# Sensor2.net
KiCad netlist of a schematic drawn in Altium Designer
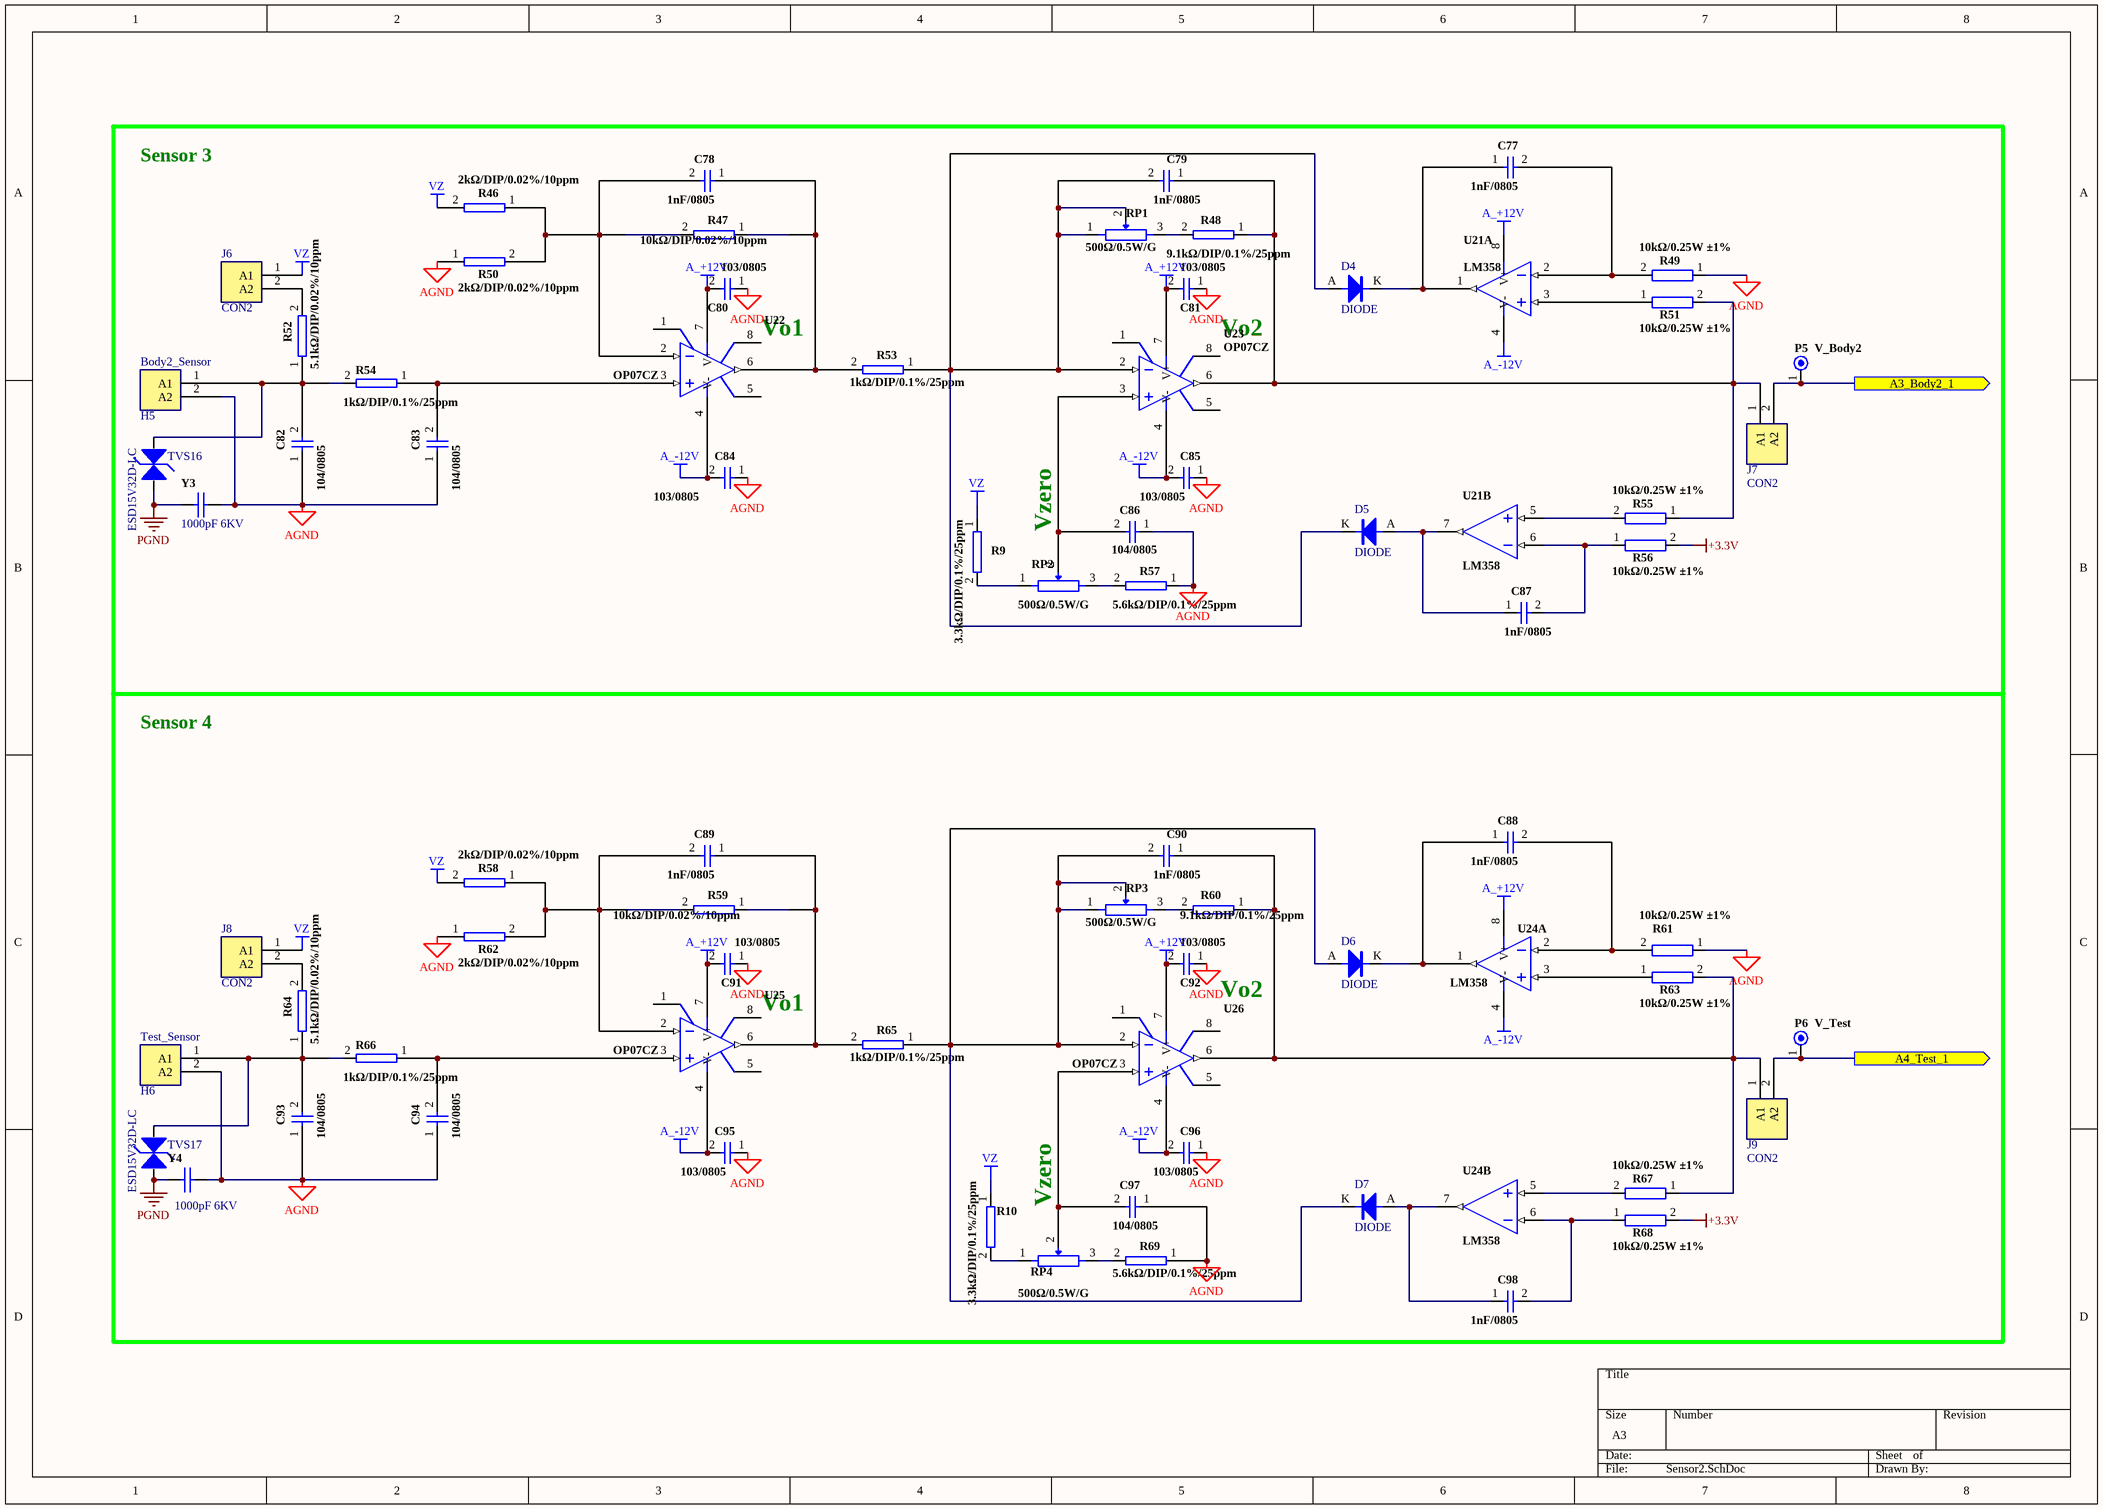
[diagram p0: Sensor2.SchDoc]

(export (version "E")
  (design (tool "Eeschema 10.0.6"))
  (components
    (comp (ref "C77")
      (value "1nF/0805")
      (footprint "C0805")
      (description "贴片电容 1nF/25V ±1% C0805")
      (libsource (lib "COOLCONTROL") (part "CAP"))
    )
    (comp (ref "C78")
      (value "1nF/0805")
      (footprint "C0805")
      (description "贴片电容 1nF/25V ±1% C0805")
      (libsource (lib "COOLCONTROL") (part "CAP"))
    )
    (comp (ref "C79")
      (value "1nF/0805")
      (footprint "C0805")
      (description "贴片电容 1nF/25V ±1% C0805")
      (libsource (lib "COOLCONTROL") (part "CAP"))
    )
    (comp (ref "C80")
      (value "103/0805")
      (footprint "C0805")
      (description "贴片电容 103/25V ±1% C0805")
      (libsource (lib "COOLCONTROL") (part "CAP"))
    )
    (comp (ref "C81")
      (value "103/0805")
      (footprint "C0805")
      (description "贴片电容 103/25V ±1% C0805")
      (libsource (lib "COOLCONTROL") (part "CAP"))
    )
    (comp (ref "C82")
      (value "104/0805")
      (footprint "C0805")
      (description "贴片电容 104/25V ±1% C0805")
      (libsource (lib "COOLCONTROL") (part "CAP"))
    )
    (comp (ref "C83")
      (value "104/0805")
      (footprint "C0805")
      (description "贴片电容 104/25V ±1% C0805")
      (libsource (lib "COOLCONTROL") (part "CAP"))
    )
    (comp (ref "C84")
      (value "103/0805")
      (footprint "C0805")
      (description "贴片电容 103/25V ±1% C0805")
      (libsource (lib "COOLCONTROL") (part "CAP"))
    )
    (comp (ref "C85")
      (value "103/0805")
      (footprint "C0805")
      (description "贴片电容 103/25V ±1% C0805")
      (libsource (lib "COOLCONTROL") (part "CAP"))
    )
    (comp (ref "C86")
      (value "104/0805")
      (footprint "C0805")
      (description "贴片电容 104/25V ±1% C0805")
      (libsource (lib "COOLCONTROL") (part "CAP"))
    )
    (comp (ref "C87")
      (value "1nF/0805")
      (footprint "C0805")
      (description "贴片电容 1nF/25V ±1% C0805")
      (libsource (lib "COOLCONTROL") (part "CAP"))
    )
    (comp (ref "C88")
      (value "1nF/0805")
      (footprint "C0805")
      (description "贴片电容 1nF/25V ±1% C0805")
      (libsource (lib "COOLCONTROL") (part "CAP"))
    )
    (comp (ref "C89")
      (value "1nF/0805")
      (footprint "C0805")
      (description "贴片电容 1nF/25V ±1% C0805")
      (libsource (lib "COOLCONTROL") (part "CAP"))
    )
    (comp (ref "C90")
      (value "1nF/0805")
      (footprint "C0805")
      (description "贴片电容 1nF/25V ±1% C0805")
      (libsource (lib "COOLCONTROL") (part "CAP"))
    )
    (comp (ref "C91")
      (value "103/0805")
      (footprint "C0805")
      (description "贴片电容 103/25V ±1% C0805")
      (libsource (lib "COOLCONTROL") (part "CAP"))
    )
    (comp (ref "C92")
      (value "103/0805")
      (footprint "C0805")
      (description "贴片电容 103/25V ±1% C0805")
      (libsource (lib "COOLCONTROL") (part "CAP"))
    )
    (comp (ref "C93")
      (value "104/0805")
      (footprint "C0805")
      (description "贴片电容 104/25V ±1% C0805")
      (libsource (lib "COOLCONTROL") (part "CAP"))
    )
    (comp (ref "C94")
      (value "104/0805")
      (footprint "C0805")
      (description "贴片电容 104/25V ±1% C0805")
      (libsource (lib "COOLCONTROL") (part "CAP"))
    )
    (comp (ref "C95")
      (value "103/0805")
      (footprint "C0805")
      (description "贴片电容 103/25V ±1% C0805")
      (libsource (lib "COOLCONTROL") (part "CAP"))
    )
    (comp (ref "C96")
      (value "103/0805")
      (footprint "C0805")
      (description "贴片电容 103/25V ±1% C0805")
      (libsource (lib "COOLCONTROL") (part "CAP"))
    )
    (comp (ref "C97")
      (value "104/0805")
      (footprint "C0805")
      (description "贴片电容 104/25V ±1% C0805")
      (libsource (lib "COOLCONTROL") (part "CAP"))
    )
    (comp (ref "C98")
      (value "1nF/0805")
      (footprint "C0805")
      (description "贴片电容 1nF/25V ±1% C0805")
      (libsource (lib "COOLCONTROL") (part "CAP"))
    )
    (comp (ref "D4")
      (value "DIODE")
      (footprint "SOD123")
      (description "高速开关二极管 IN4148 1V 150mA SOD123")
      (libsource (lib "") (part "DIODE_1"))
    )
    (comp (ref "D5")
      (value "DIODE")
      (footprint "SOD123")
      (description "高速开关二极管 IN4148 1V 150mA SOD123")
      (libsource (lib "COOLCONTROL") (part "DIODE"))
    )
    (comp (ref "D6")
      (value "DIODE")
      (footprint "SOD123")
      (description "高速开关二极管 IN4148 1V 150mA SOD123")
      (libsource (lib "") (part "DIODE_1"))
    )
    (comp (ref "D7")
      (value "DIODE")
      (footprint "SOD123")
      (description "高速开关二极管 IN4148 1V 150mA SOD123")
      (libsource (lib "COOLCONTROL") (part "DIODE"))
    )
    (comp (ref "H5")
      (value "Body2_Sensor")
      (footprint "XH2")
      (description "插座式端子 XH2.54-2P 250V(DC/AC) 3A")
      (libsource (lib "COOLCONTROL") (part "CON2"))
    )
    (comp (ref "H6")
      (value "Test_Sensor")
      (footprint "XH2")
      (description "插座式端子 XH2.54-2P 250V(DC/AC) 3A")
      (libsource (lib "COOLCONTROL") (part "CON2"))
    )
    (comp (ref "J6")
      (value "CON2")
      (footprint "2Pin-2.54")
      (description "单排排针（2针）2.54mm 2Pin-2.54")
      (libsource (lib "COOLCONTROL") (part "CON2"))
    )
    (comp (ref "J7")
      (value "CON2")
      (footprint "2Pin-2.54")
      (description "单排排针（2针）2.54mm 2Pin-2.54")
      (libsource (lib "") (part "CON2_1"))
    )
    (comp (ref "J8")
      (value "CON2")
      (footprint "2Pin-2.54")
      (description "单排排针（2针）2.54mm 2Pin-2.54")
      (libsource (lib "COOLCONTROL") (part "CON2"))
    )
    (comp (ref "J9")
      (value "CON2")
      (footprint "2Pin-2.54")
      (description "单排排针（2针）2.54mm 2Pin-2.54")
      (libsource (lib "") (part "CON2_1"))
    )
    (comp (ref "P5")
      (value "V_Body2")
      (footprint "COOLCONTROL:TESTSMD")
      (libsource (lib "COOLCONTROL") (part "CON1"))
    )
    (comp (ref "P6")
      (value "V_Test")
      (footprint "COOLCONTROL:TESTSMD")
      (libsource (lib "COOLCONTROL") (part "CON1"))
    )
    (comp (ref "R9")
      (value "3.3kΩ/DIP/0.1%/25ppm")
      (footprint "COOLCONTROL:AXIAL0.4")
      (description "高精度电阻 3.3kΩ DIP 0.25W ±0.1% 25ppm AXIAL0.4")
      (libsource (lib "COOLCONTROL") (part "RES2"))
    )
    (comp (ref "R10")
      (value "3.3kΩ/DIP/0.1%/25ppm")
      (footprint "COOLCONTROL:AXIAL0.4")
      (description "高精度电阻 3.3kΩ DIP 0.25W ±0.1% 25ppm AXIAL0.4")
      (libsource (lib "COOLCONTROL") (part "RES2"))
    )
    (comp (ref "R46")
      (value "2kΩ/DIP/0.02%/10ppm")
      (footprint "AXIAL-0.6-R")
      (description "高精度电阻 2kΩ DIP 0.25W ±0.02% 10ppm AXIAL-0.6-R")
      (libsource (lib "COOLCONTROL") (part "RES2"))
    )
    (comp (ref "R47")
      (value "10kΩ/DIP/0.02%/10ppm")
      (footprint "AXIAL-0.6-R")
      (description "高精度电阻 10kΩ DIP 0.25W ±0.02% 10ppm AXIAL-0.6-R")
      (libsource (lib "COOLCONTROL") (part "RES2"))
    )
    (comp (ref "R48")
      (value "9.1kΩ/DIP/0.1%/25ppm")
      (footprint "COOLCONTROL:AXIAL0.4")
      (description "高精度电阻 9.1kΩ DIP 0.25W ±0.1% 25ppm AXIAL0.4")
      (libsource (lib "COOLCONTROL") (part "RES2"))
    )
    (comp (ref "R49")
      (value "10kΩ/0.25W ±1%")
      (footprint "R0805")
      (description "贴片电阻 10kΩ 0.25W ±1% R0805")
      (libsource (lib "") (part "RES2_1"))
    )
    (comp (ref "R50")
      (value "2kΩ/DIP/0.02%/10ppm")
      (footprint "AXIAL-0.6-R")
      (description "高精度电阻 2kΩ DIP 0.25W ±0.02% 10ppm AXIAL-0.6-R")
      (libsource (lib "COOLCONTROL") (part "RES2"))
    )
    (comp (ref "R51")
      (value "10kΩ/0.25W ±1%")
      (footprint "R0805")
      (description "贴片电阻 10kΩ 0.25W ±1% R0805")
      (libsource (lib "") (part "RES2_2"))
    )
    (comp (ref "R52")
      (value "5.1kΩ/DIP/0.02%/10ppm")
      (footprint "AXIAL-0.6-R")
      (description "高精度电阻 5.1kΩ DIP 0.25W ±0.02% 10ppm AXIAL-0.6-R")
      (libsource (lib "COOLCONTROL") (part "RES2"))
    )
    (comp (ref "R53")
      (value "1kΩ/DIP/0.1%/25ppm")
      (footprint "COOLCONTROL:AXIAL0.4")
      (description "高精度电阻 1kΩ DIP 0.25W ±0.1% 25ppm AXIAL0.4")
      (libsource (lib "COOLCONTROL") (part "RES2"))
    )
    (comp (ref "R54")
      (value "1kΩ/DIP/0.1%/25ppm")
      (footprint "COOLCONTROL:AXIAL0.4")
      (description "高精度电阻 1kΩ DIP 0.25W ±0.1% 25ppm AXIAL0.4")
      (libsource (lib "COOLCONTROL") (part "RES2"))
    )
    (comp (ref "R55")
      (value "10kΩ/0.25W ±1%")
      (footprint "R0805")
      (description "贴片电阻 10kΩ 0.25W ±1% R0805")
      (libsource (lib "") (part "RES2_1"))
    )
    (comp (ref "R56")
      (value "10kΩ/0.25W ±1%")
      (footprint "R0805")
      (description "贴片电阻 10kΩ 0.25W ±1% R0805")
      (libsource (lib "") (part "RES2_2"))
    )
    (comp (ref "R57")
      (value "5.6kΩ/DIP/0.1%/25ppm")
      (footprint "COOLCONTROL:AXIAL0.4")
      (description "高精度电阻 5.6kΩ DIP 0.25W ±0.1% 25ppm AXIAL0.4")
      (libsource (lib "COOLCONTROL") (part "RES2"))
    )
    (comp (ref "R58")
      (value "2kΩ/DIP/0.02%/10ppm")
      (footprint "AXIAL-0.6-R")
      (description "高精度电阻 2kΩ DIP 0.25W ±0.02% 10ppm AXIAL-0.6-R")
      (libsource (lib "COOLCONTROL") (part "RES2"))
    )
    (comp (ref "R59")
      (value "10kΩ/DIP/0.02%/10ppm")
      (footprint "AXIAL-0.6-R")
      (description "高精度电阻 10kΩ DIP 0.25W ±0.02% 10ppm AXIAL-0.6-R")
      (libsource (lib "COOLCONTROL") (part "RES2"))
    )
    (comp (ref "R60")
      (value "9.1kΩ/DIP/0.1%/25ppm")
      (footprint "COOLCONTROL:AXIAL0.4")
      (description "高精度电阻 9.1kΩ DIP 0.25W ±0.1% 25ppm AXIAL0.4")
      (libsource (lib "COOLCONTROL") (part "RES2"))
    )
    (comp (ref "R61")
      (value "10kΩ/0.25W ±1%")
      (footprint "R0805")
      (description "贴片电阻 10kΩ 0.25W ±1% R0805")
      (libsource (lib "") (part "RES2_1"))
    )
    (comp (ref "R62")
      (value "2kΩ/DIP/0.02%/10ppm")
      (footprint "AXIAL-0.6-R")
      (description "高精度电阻 2kΩ DIP 0.25W ±0.02% 10ppm AXIAL-0.6-R")
      (libsource (lib "COOLCONTROL") (part "RES2"))
    )
    (comp (ref "R63")
      (value "10kΩ/0.25W ±1%")
      (footprint "R0805")
      (description "贴片电阻 10kΩ 0.25W ±1% R0805")
      (libsource (lib "") (part "RES2_2"))
    )
    (comp (ref "R64")
      (value "5.1kΩ/DIP/0.02%/10ppm")
      (footprint "AXIAL-0.6-R")
      (description "高精度电阻 5.1kΩ DIP 0.25W ±0.02% 10ppm AXIAL-0.6-R")
      (libsource (lib "COOLCONTROL") (part "RES2"))
    )
    (comp (ref "R65")
      (value "1kΩ/DIP/0.1%/25ppm")
      (footprint "COOLCONTROL:AXIAL0.4")
      (description "高精度电阻 1kΩ DIP 0.25W ±0.1% 25ppm AXIAL0.4")
      (libsource (lib "COOLCONTROL") (part "RES2"))
    )
    (comp (ref "R66")
      (value "1kΩ/DIP/0.1%/25ppm")
      (footprint "AXIAL0.4")
      (description "高精度电阻 1kΩ DIP 0.25W ±0.1% 25ppm AXIAL0.4")
      (libsource (lib "COOLCONTROL") (part "RES2"))
    )
    (comp (ref "R67")
      (value "10kΩ/0.25W ±1%")
      (footprint "R0805")
      (description "贴片电阻 10kΩ 0.25W ±1% R0805")
      (libsource (lib "") (part "RES2_1"))
    )
    (comp (ref "R68")
      (value "10kΩ/0.25W ±1%")
      (footprint "R0805")
      (description "贴片电阻 10kΩ 0.25W ±1% R0805")
      (libsource (lib "") (part "RES2_2"))
    )
    (comp (ref "R69")
      (value "5.6kΩ/DIP/0.1%/25ppm")
      (footprint "COOLCONTROL:AXIAL0.4")
      (description "高精度电阻 5.6kΩ DIP 0.25W ±0.1% 25ppm AXIAL0.4")
      (libsource (lib "COOLCONTROL") (part "RES2"))
    )
    (comp (ref "RP1")
      (value "500Ω/0.5W/G")
      (footprint "3224W")
      (description "高精密可调电位器 500Ω/0.5W/G 3224W")
      (libsource (lib "COOLCONTROL") (part "RPOT"))
    )
    (comp (ref "RP2")
      (value "500Ω/0.5W/G")
      (footprint "3224W")
      (description "高精密可调电位器 500Ω/0.5W/G 3224W")
      (libsource (lib "COOLCONTROL") (part "RPOT"))
    )
    (comp (ref "RP3")
      (value "500Ω/0.5W/G")
      (footprint "3224W")
      (description "高精密可调电位器 500Ω/0.5W/G 3224W")
      (libsource (lib "COOLCONTROL") (part "RPOT"))
    )
    (comp (ref "RP4")
      (value "500Ω/0.5W/G")
      (footprint "3224W")
      (description "高精密可调电位器 500Ω/0.5W/G 3224W")
      (libsource (lib "COOLCONTROL") (part "RPOT"))
    )
    (comp (ref "TVS16")
      (value "ESD15V32D-LC")
      (footprint "SOD323")
      (description "ESD静电二极管 ESD15V32D-LC 15V 15KV 40A SOD323")
      (libsource (lib "COOLCONTROL") (part "TVS"))
    )
    (comp (ref "TVS17")
      (value "ESD15V32D-LC")
      (footprint "SOD323")
      (description "ESD静电二极管 ESD15V32D-LC 15V 15KV 40A SOD323")
      (libsource (lib "COOLCONTROL") (part "TVS"))
    )
    (comp (ref "U21")
      (value "LM358")
      (footprint "SO-8")
      (description "双运算放大器 LM358 SO-8")
      (libsource (lib "COOLCONTROL") (part "MC1458D"))
    )
    (comp (ref "U22")
      (value "OP07CZ")
      (footprint "SO-8")
      (description "运算放大器 OP07CZ SO-8")
      (libsource (lib "COOLCONTROL") (part "OP07CZ"))
    )
    (comp (ref "U23")
      (value "OP07CZ")
      (footprint "SO-8")
      (description "运算放大器 OP07CZ SO-8")
      (libsource (lib "COOLCONTROL") (part "OP07CZ"))
    )
    (comp (ref "U24")
      (value "LM358")
      (footprint "SO-8")
      (description "双运算放大器 LM358 SO-8")
      (libsource (lib "COOLCONTROL") (part "MC1458D"))
    )
    (comp (ref "U25")
      (value "OP07CZ")
      (footprint "SO-8")
      (description "运算放大器 OP07CZ SO-8")
      (libsource (lib "COOLCONTROL") (part "OP07CZ"))
    )
    (comp (ref "U26")
      (value "OP07CZ")
      (footprint "SO-8")
      (description "运算放大器 OP07CZ SO-8")
      (libsource (lib "COOLCONTROL") (part "OP07CZ"))
    )
    (comp (ref "Y3")
      (value "1000pF 6KV")
      (footprint "CY1002")
      (description "安规电容 1000pF 6KV ±20% CY1002")
      (libsource (lib "") (part "CAP_1"))
    )
    (comp (ref "Y4")
      (value "1000pF 6KV")
      (footprint "COOLCONTROL:CY1002")
      (description "安规电容 1000pF 6KV ±20% CY1002")
      (libsource (lib "") (part "CAP_1"))
    )
  )
  (nets
    (net (code "1") (name "+3.3V") (class "Default")
      (node (ref "R56") (pin "2") (pintype "passive"))
      (node (ref "R68") (pin "2") (pintype "passive"))
    )
    (net (code "2") (name "/A3_Body2_1") (class "Default")
      (node (ref "J7") (pin "2") (pinfunction "A2_2") (pintype "passive"))
      (node (ref "P5") (pin "1") (pintype "passive"))
    )
    (net (code "3") (name "/A4_Test_1") (class "Default")
      (node (ref "J9") (pin "2") (pinfunction "A2_2") (pintype "passive"))
      (node (ref "P6") (pin "1") (pintype "passive"))
    )
    (net (code "4") (name "AGND") (class "Default")
      (node (ref "C80") (pin "1") (pintype "passive"))
      (node (ref "C81") (pin "1") (pintype "passive"))
      (node (ref "C82") (pin "1") (pintype "passive"))
      (node (ref "C83") (pin "1") (pintype "passive"))
      (node (ref "C84") (pin "1") (pintype "passive"))
      (node (ref "C85") (pin "1") (pintype "passive"))
      (node (ref "C86") (pin "1") (pintype "passive"))
      (node (ref "C91") (pin "1") (pintype "passive"))
      (node (ref "C92") (pin "1") (pintype "passive"))
      (node (ref "C93") (pin "1") (pintype "passive"))
      (node (ref "C94") (pin "1") (pintype "passive"))
      (node (ref "C95") (pin "1") (pintype "passive"))
      (node (ref "C96") (pin "1") (pintype "passive"))
      (node (ref "C97") (pin "1") (pintype "passive"))
      (node (ref "H5") (pin "2") (pinfunction "A2_2") (pintype "passive"))
      (node (ref "H6") (pin "2") (pinfunction "A2_2") (pintype "passive"))
      (node (ref "R49") (pin "1") (pintype "passive"))
      (node (ref "R50") (pin "1") (pintype "passive"))
      (node (ref "R57") (pin "1") (pintype "passive"))
      (node (ref "R61") (pin "1") (pintype "passive"))
      (node (ref "R62") (pin "1") (pintype "passive"))
      (node (ref "R69") (pin "1") (pintype "passive"))
      (node (ref "Y3") (pin "2") (pinfunction "2_2") (pintype "passive"))
      (node (ref "Y4") (pin "2") (pinfunction "2_2") (pintype "passive"))
    )
    (net (code "5") (name "A_+12V") (class "Default")
      (node (ref "C80") (pin "2") (pintype "passive"))
      (node (ref "C81") (pin "2") (pintype "passive"))
      (node (ref "C91") (pin "2") (pintype "passive"))
      (node (ref "C92") (pin "2") (pintype "passive"))
      (node (ref "U21") (pin "8") (pinfunction "V+_8") (pintype "power_in"))
      (node (ref "U22") (pin "7") (pinfunction "V+_7") (pintype "power_in"))
      (node (ref "U23") (pin "7") (pinfunction "V+_7") (pintype "power_in"))
      (node (ref "U24") (pin "8") (pinfunction "V+_8") (pintype "power_in"))
      (node (ref "U25") (pin "7") (pinfunction "V+_7") (pintype "power_in"))
      (node (ref "U26") (pin "7") (pinfunction "V+_7") (pintype "power_in"))
    )
    (net (code "6") (name "A_-12V") (class "Default")
      (node (ref "C84") (pin "2") (pintype "passive"))
      (node (ref "C85") (pin "2") (pintype "passive"))
      (node (ref "C95") (pin "2") (pintype "passive"))
      (node (ref "C96") (pin "2") (pintype "passive"))
      (node (ref "U21") (pin "4") (pinfunction "V-_4") (pintype "power_in"))
      (node (ref "U22") (pin "4") (pinfunction "V-_4") (pintype "power_in"))
      (node (ref "U23") (pin "4") (pinfunction "V-_4") (pintype "power_in"))
      (node (ref "U24") (pin "4") (pinfunction "V-_4") (pintype "power_in"))
      (node (ref "U25") (pin "4") (pinfunction "V-_4") (pintype "power_in"))
      (node (ref "U26") (pin "4") (pinfunction "V-_4") (pintype "power_in"))
    )
    (net (code "7") (name "Net-(C77-Pad1)") (class "Default")
      (node (ref "C77") (pin "1") (pintype "passive"))
      (node (ref "D4") (pin "K") (pinfunction "K_K") (pintype "passive"))
      (node (ref "U21") (pin "1") (pintype "output"))
    )
    (net (code "8") (name "Net-(C77-Pad2)") (class "Default")
      (node (ref "C77") (pin "2") (pintype "passive"))
      (node (ref "R49") (pin "2") (pintype "passive"))
      (node (ref "U21") (pin "2") (pintype "input"))
    )
    (net (code "9") (name "Net-(C78-Pad1)") (class "Default")
      (node (ref "C78") (pin "1") (pintype "passive"))
      (node (ref "R47") (pin "1") (pintype "passive"))
      (node (ref "R53") (pin "2") (pintype "passive"))
      (node (ref "U22") (pin "6") (pintype "output"))
    )
    (net (code "10") (name "Net-(C78-Pad2)") (class "Default")
      (node (ref "C78") (pin "2") (pintype "passive"))
      (node (ref "R46") (pin "1") (pintype "passive"))
      (node (ref "R47") (pin "2") (pintype "passive"))
      (node (ref "R50") (pin "2") (pintype "passive"))
      (node (ref "U22") (pin "2") (pintype "input"))
    )
    (net (code "11") (name "Net-(C79-Pad2)") (class "Default")
      (node (ref "C79") (pin "2") (pintype "passive"))
      (node (ref "D4") (pin "A") (pinfunction "A_A") (pintype "passive"))
      (node (ref "D5") (pin "K") (pinfunction "K_K") (pintype "passive"))
      (node (ref "R53") (pin "1") (pintype "passive"))
      (node (ref "RP1") (pin "1") (pintype "passive"))
      (node (ref "RP1") (pin "2") (pintype "passive"))
      (node (ref "U23") (pin "2") (pintype "input"))
    )
    (net (code "12") (name "Net-(C83-Pad2)") (class "Default")
      (node (ref "C83") (pin "2") (pintype "passive"))
      (node (ref "R54") (pin "1") (pintype "passive"))
      (node (ref "U22") (pin "3") (pintype "input"))
    )
    (net (code "13") (name "Net-(C86-Pad2)") (class "Default")
      (node (ref "C86") (pin "2") (pintype "passive"))
      (node (ref "RP2") (pin "2") (pintype "passive"))
      (node (ref "U23") (pin "3") (pintype "input"))
    )
    (net (code "14") (name "Net-(C87-Pad1)") (class "Default")
      (node (ref "C87") (pin "1") (pintype "passive"))
      (node (ref "D5") (pin "A") (pinfunction "A_A") (pintype "passive"))
      (node (ref "U21") (pin "7") (pintype "output"))
    )
    (net (code "15") (name "Net-(C87-Pad2)") (class "Default")
      (node (ref "C87") (pin "2") (pintype "passive"))
      (node (ref "R56") (pin "1") (pintype "passive"))
      (node (ref "U21") (pin "6") (pintype "input"))
    )
    (net (code "16") (name "Net-(C88-Pad1)") (class "Default")
      (node (ref "C88") (pin "1") (pintype "passive"))
      (node (ref "D6") (pin "K") (pinfunction "K_K") (pintype "passive"))
      (node (ref "U24") (pin "1") (pintype "output"))
    )
    (net (code "17") (name "Net-(C88-Pad2)") (class "Default")
      (node (ref "C88") (pin "2") (pintype "passive"))
      (node (ref "R61") (pin "2") (pintype "passive"))
      (node (ref "U24") (pin "2") (pintype "input"))
    )
    (net (code "18") (name "Net-(C89-Pad1)") (class "Default")
      (node (ref "C89") (pin "1") (pintype "passive"))
      (node (ref "R59") (pin "1") (pintype "passive"))
      (node (ref "R65") (pin "2") (pintype "passive"))
      (node (ref "U25") (pin "6") (pintype "output"))
    )
    (net (code "19") (name "Net-(C89-Pad2)") (class "Default")
      (node (ref "C89") (pin "2") (pintype "passive"))
      (node (ref "R58") (pin "1") (pintype "passive"))
      (node (ref "R59") (pin "2") (pintype "passive"))
      (node (ref "R62") (pin "2") (pintype "passive"))
      (node (ref "U25") (pin "2") (pintype "input"))
    )
    (net (code "20") (name "Net-(C90-Pad2)") (class "Default")
      (node (ref "C90") (pin "2") (pintype "passive"))
      (node (ref "D6") (pin "A") (pinfunction "A_A") (pintype "passive"))
      (node (ref "D7") (pin "K") (pinfunction "K_K") (pintype "passive"))
      (node (ref "R65") (pin "1") (pintype "passive"))
      (node (ref "RP3") (pin "1") (pintype "passive"))
      (node (ref "RP3") (pin "2") (pintype "passive"))
      (node (ref "U26") (pin "2") (pintype "input"))
    )
    (net (code "21") (name "Net-(C94-Pad2)") (class "Default")
      (node (ref "C94") (pin "2") (pintype "passive"))
      (node (ref "R66") (pin "1") (pintype "passive"))
      (node (ref "U25") (pin "3") (pintype "input"))
    )
    (net (code "22") (name "Net-(C97-Pad2)") (class "Default")
      (node (ref "C97") (pin "2") (pintype "passive"))
      (node (ref "RP4") (pin "2") (pintype "passive"))
      (node (ref "U26") (pin "3") (pintype "input"))
    )
    (net (code "23") (name "Net-(C98-Pad1)") (class "Default")
      (node (ref "C98") (pin "1") (pintype "passive"))
      (node (ref "D7") (pin "A") (pinfunction "A_A") (pintype "passive"))
      (node (ref "U24") (pin "7") (pintype "output"))
    )
    (net (code "24") (name "Net-(C98-Pad2)") (class "Default")
      (node (ref "C98") (pin "2") (pintype "passive"))
      (node (ref "R68") (pin "1") (pintype "passive"))
      (node (ref "U24") (pin "6") (pintype "input"))
    )
    (net (code "25") (name "Net-(H5-A1)") (class "Default")
      (node (ref "C82") (pin "2") (pintype "passive"))
      (node (ref "H5") (pin "1") (pinfunction "A1_1") (pintype "passive"))
      (node (ref "R52") (pin "1") (pintype "passive"))
      (node (ref "R54") (pin "2") (pintype "passive"))
      (node (ref "TVS16") (pin "1") (pinfunction "1_1") (pintype "passive"))
    )
    (net (code "26") (name "Net-(H6-A1)") (class "Default")
      (node (ref "C93") (pin "2") (pintype "passive"))
      (node (ref "H6") (pin "1") (pinfunction "A1_1") (pintype "passive"))
      (node (ref "R64") (pin "1") (pintype "passive"))
      (node (ref "R66") (pin "2") (pintype "passive"))
      (node (ref "TVS17") (pin "1") (pinfunction "1_1") (pintype "passive"))
    )
    (net (code "27") (name "Net-(J6-A2)") (class "Default")
      (node (ref "J6") (pin "2") (pinfunction "A2_2") (pintype "passive"))
      (node (ref "R52") (pin "2") (pintype "passive"))
    )
    (net (code "28") (name "Net-(J7-A1)") (class "Default")
      (node (ref "C79") (pin "1") (pintype "passive"))
      (node (ref "J7") (pin "1") (pinfunction "A1_1") (pintype "passive"))
      (node (ref "R48") (pin "1") (pintype "passive"))
      (node (ref "R51") (pin "2") (pintype "passive"))
      (node (ref "R55") (pin "1") (pintype "passive"))
      (node (ref "U23") (pin "6") (pintype "output"))
    )
    (net (code "29") (name "Net-(J8-A2)") (class "Default")
      (node (ref "J8") (pin "2") (pinfunction "A2_2") (pintype "passive"))
      (node (ref "R64") (pin "2") (pintype "passive"))
    )
    (net (code "30") (name "Net-(J9-A1)") (class "Default")
      (node (ref "C90") (pin "1") (pintype "passive"))
      (node (ref "J9") (pin "1") (pinfunction "A1_1") (pintype "passive"))
      (node (ref "R60") (pin "1") (pintype "passive"))
      (node (ref "R63") (pin "2") (pintype "passive"))
      (node (ref "R67") (pin "1") (pintype "passive"))
      (node (ref "U26") (pin "6") (pintype "output"))
    )
    (net (code "31") (name "Net-(R9-Pad2)") (class "Default")
      (node (ref "R9") (pin "2") (pintype "passive"))
      (node (ref "RP2") (pin "1") (pintype "passive"))
    )
    (net (code "32") (name "Net-(R10-Pad2)") (class "Default")
      (node (ref "R10") (pin "2") (pintype "passive"))
      (node (ref "RP4") (pin "1") (pintype "passive"))
    )
    (net (code "33") (name "Net-(R48-Pad2)") (class "Default")
      (node (ref "R48") (pin "2") (pintype "passive"))
      (node (ref "RP1") (pin "3") (pintype "passive"))
    )
    (net (code "34") (name "Net-(R51-Pad1)") (class "Default")
      (node (ref "R51") (pin "1") (pintype "passive"))
      (node (ref "U21") (pin "3") (pintype "input"))
    )
    (net (code "35") (name "Net-(R55-Pad2)") (class "Default")
      (node (ref "R55") (pin "2") (pintype "passive"))
      (node (ref "U21") (pin "5") (pintype "input"))
    )
    (net (code "36") (name "Net-(R57-Pad2)") (class "Default")
      (node (ref "R57") (pin "2") (pintype "passive"))
      (node (ref "RP2") (pin "3") (pintype "passive"))
    )
    (net (code "37") (name "Net-(R60-Pad2)") (class "Default")
      (node (ref "R60") (pin "2") (pintype "passive"))
      (node (ref "RP3") (pin "3") (pintype "passive"))
    )
    (net (code "38") (name "Net-(R63-Pad1)") (class "Default")
      (node (ref "R63") (pin "1") (pintype "passive"))
      (node (ref "U24") (pin "3") (pintype "input"))
    )
    (net (code "39") (name "Net-(R67-Pad2)") (class "Default")
      (node (ref "R67") (pin "2") (pintype "passive"))
      (node (ref "U24") (pin "5") (pintype "input"))
    )
    (net (code "40") (name "Net-(R69-Pad2)") (class "Default")
      (node (ref "R69") (pin "2") (pintype "passive"))
      (node (ref "RP4") (pin "3") (pintype "passive"))
    )
    (net (code "41") (name "PGND") (class "Default")
      (node (ref "TVS16") (pin "2") (pinfunction "2_2") (pintype "passive"))
      (node (ref "TVS17") (pin "2") (pinfunction "2_2") (pintype "passive"))
      (node (ref "Y3") (pin "1") (pinfunction "1_1") (pintype "passive"))
      (node (ref "Y4") (pin "1") (pinfunction "1_1") (pintype "passive"))
    )
    (net (code "42") (name "VZ") (class "Default")
      (node (ref "J6") (pin "1") (pinfunction "A1_1") (pintype "passive"))
      (node (ref "J8") (pin "1") (pinfunction "A1_1") (pintype "passive"))
      (node (ref "R10") (pin "1") (pintype "passive"))
      (node (ref "R46") (pin "2") (pintype "passive"))
      (node (ref "R58") (pin "2") (pintype "passive"))
      (node (ref "R9") (pin "1") (pintype "passive"))
    )
    (net (code "43") (name "unconnected-(U22-Pad1)") (class "Default")
      (node (ref "U22") (pin "1") (pintype "passive"))
    )
    (net (code "44") (name "unconnected-(U22-Pad5)") (class "Default")
      (node (ref "U22") (pin "5") (pintype "passive"))
    )
    (net (code "45") (name "unconnected-(U22-Pad8)") (class "Default")
      (node (ref "U22") (pin "8") (pintype "passive"))
    )
    (net (code "46") (name "unconnected-(U23-Pad1)") (class "Default")
      (node (ref "U23") (pin "1") (pintype "passive"))
    )
    (net (code "47") (name "unconnected-(U23-Pad5)") (class "Default")
      (node (ref "U23") (pin "5") (pintype "passive"))
    )
    (net (code "48") (name "unconnected-(U23-Pad8)") (class "Default")
      (node (ref "U23") (pin "8") (pintype "passive"))
    )
    (net (code "49") (name "unconnected-(U25-Pad1)") (class "Default")
      (node (ref "U25") (pin "1") (pintype "passive"))
    )
    (net (code "50") (name "unconnected-(U25-Pad5)") (class "Default")
      (node (ref "U25") (pin "5") (pintype "passive"))
    )
    (net (code "51") (name "unconnected-(U25-Pad8)") (class "Default")
      (node (ref "U25") (pin "8") (pintype "passive"))
    )
    (net (code "52") (name "unconnected-(U26-Pad1)") (class "Default")
      (node (ref "U26") (pin "1") (pintype "passive"))
    )
    (net (code "53") (name "unconnected-(U26-Pad5)") (class "Default")
      (node (ref "U26") (pin "5") (pintype "passive"))
    )
    (net (code "54") (name "unconnected-(U26-Pad8)") (class "Default")
      (node (ref "U26") (pin "8") (pintype "passive"))
    )
  )
)
